# power_fix.net
KiCad netlist of a schematic drawn in Altium Designer
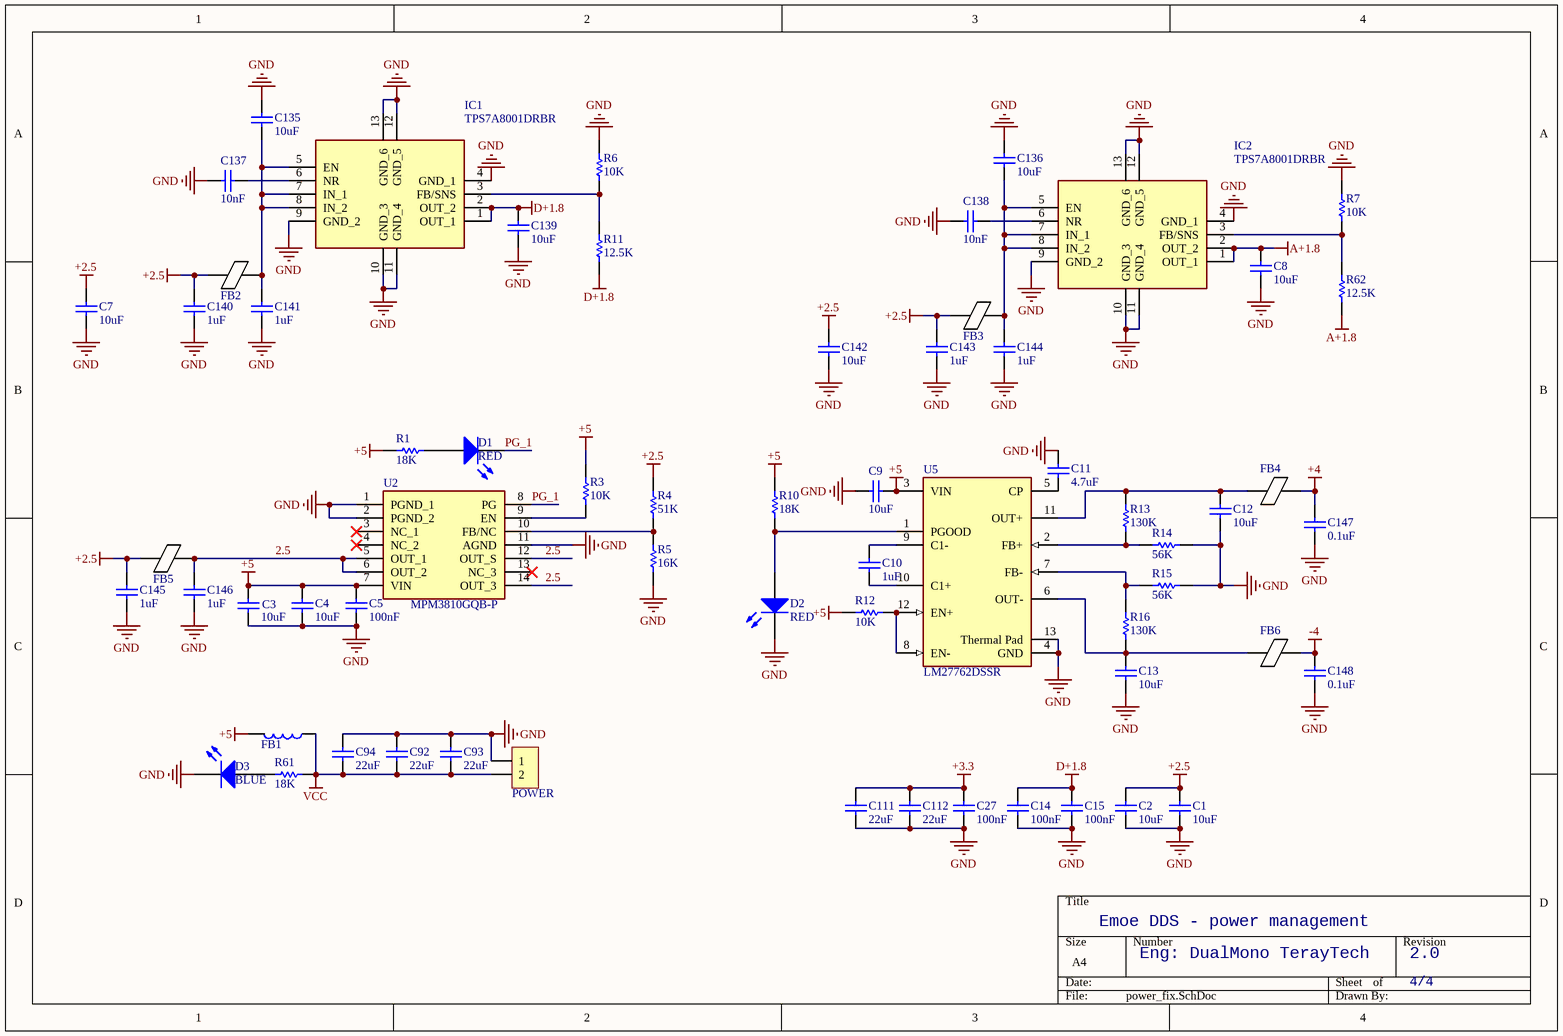
[diagram p0: power_fix.SchDoc]

(export (version "E")
  (design (tool "Eeschema 10.0.6"))
  (components
    (comp (ref "C1")
      (value "10uF")
      (footprint "1608[0603]")
      (description "Capacitor")
      (fields (field (name "PUBLISHER") "Altium Limited"))
      (libsource (lib "My Footprint") (part "CAP"))
    )
    (comp (ref "C2")
      (value "10uF")
      (footprint "1608[0603]")
      (description "Capacitor")
      (fields (field (name "PUBLISHER") "Altium Limited"))
      (libsource (lib "My Footprint") (part "CAP"))
    )
    (comp (ref "C3")
      (value "10uF")
      (footprint "1608[0603]")
      (description "Capacitor")
      (fields (field (name "PUBLISHER") "Altium Limited"))
      (libsource (lib "My Footprint") (part "CAP"))
    )
    (comp (ref "C4")
      (value "10uF")
      (footprint "1608[0603]")
      (description "Capacitor")
      (fields (field (name "PUBLISHER") "Altium Limited"))
      (libsource (lib "My Footprint") (part "CAP"))
    )
    (comp (ref "C5")
      (value "100nF")
      (footprint "0402")
      (description "Capacitor")
      (fields (field (name "PUBLISHER") "Altium Limited"))
      (libsource (lib "My Footprint") (part "CAP"))
    )
    (comp (ref "C7")
      (value "10uF")
      (footprint "1608[0603]")
      (description "Capacitor")
      (fields (field (name "PUBLISHER") "Altium Limited"))
      (libsource (lib "My Footprint") (part "CAP"))
    )
    (comp (ref "C8")
      (value "10uF")
      (footprint "0603_C")
      (description "Capacitor")
      (fields (field (name "PUBLISHER") "Altium Limited"))
      (libsource (lib "My Footprint") (part "CAP"))
    )
    (comp (ref "C9")
      (value "10uF")
      (footprint "1608[0603]")
      (description "Capacitor")
      (fields (field (name "PUBLISHER") "Altium Limited"))
      (libsource (lib "My Footprint") (part "CAP"))
    )
    (comp (ref "C10")
      (value "1uF")
      (footprint "0402")
      (description "Capacitor")
      (fields (field (name "PUBLISHER") "Altium Limited"))
      (libsource (lib "My Footprint") (part "CAP"))
    )
    (comp (ref "C11")
      (value "4.7uF")
      (footprint "1608[0603]")
      (description "Capacitor")
      (fields (field (name "PUBLISHER") "Altium Limited"))
      (libsource (lib "My Footprint") (part "CAP"))
    )
    (comp (ref "C12")
      (value "10uF")
      (footprint "1608[0603]")
      (description "Capacitor")
      (fields (field (name "PUBLISHER") "Altium Limited"))
      (libsource (lib "My Footprint") (part "CAP"))
    )
    (comp (ref "C13")
      (value "10uF")
      (footprint "1608[0603]")
      (description "Capacitor")
      (fields (field (name "PUBLISHER") "Altium Limited"))
      (libsource (lib "My Footprint") (part "CAP"))
    )
    (comp (ref "C14")
      (value "100nF")
      (footprint "0402")
      (description "Capacitor")
      (fields (field (name "PUBLISHER") "Altium Limited"))
      (libsource (lib "My Footprint") (part "CAP"))
    )
    (comp (ref "C15")
      (value "100nF")
      (footprint "0402")
      (description "Capacitor")
      (fields (field (name "PUBLISHER") "Altium Limited"))
      (libsource (lib "My Footprint") (part "CAP"))
    )
    (comp (ref "C27")
      (value "100nF")
      (footprint "0402")
      (description "Capacitor")
      (fields (field (name "PUBLISHER") "Altium Limited"))
      (libsource (lib "My Footprint") (part "CAP"))
    )
    (comp (ref "C92")
      (value "22uF")
      (footprint "6-0805_L")
      (description "Capacitor")
      (fields (field (name "PUBLISHER") "Altium Limited"))
      (libsource (lib "My Footprint") (part "CAP"))
    )
    (comp (ref "C93")
      (value "22uF")
      (footprint "6-0805_L")
      (description "Capacitor")
      (fields (field (name "PUBLISHER") "Altium Limited"))
      (libsource (lib "My Footprint") (part "CAP"))
    )
    (comp (ref "C94")
      (value "22uF")
      (footprint "6-0805_L")
      (description "Capacitor")
      (fields (field (name "PUBLISHER") "Altium Limited"))
      (libsource (lib "My Footprint") (part "CAP"))
    )
    (comp (ref "C111")
      (value "22uF")
      (footprint "6-0805_L")
      (description "Capacitor")
      (fields (field (name "PUBLISHER") "Altium Limited"))
      (libsource (lib "My Footprint") (part "CAP"))
    )
    (comp (ref "C112")
      (value "22uF")
      (footprint "6-0805_L")
      (description "Capacitor")
      (fields (field (name "PUBLISHER") "Altium Limited"))
      (libsource (lib "My Footprint") (part "CAP"))
    )
    (comp (ref "C135")
      (value "10uF")
      (footprint "0603_C")
      (description "Capacitor")
      (fields (field (name "PUBLISHER") "Altium Limited"))
      (libsource (lib "My Footprint") (part "CAP"))
    )
    (comp (ref "C136")
      (value "10uF")
      (footprint "0603_C")
      (description "Capacitor")
      (fields (field (name "PUBLISHER") "Altium Limited"))
      (libsource (lib "My Footprint") (part "CAP"))
    )
    (comp (ref "C137")
      (value "10nF")
      (footprint "0402L")
      (description "Capacitor")
      (fields (field (name "PUBLISHER") "Altium Limited"))
      (libsource (lib "My Footprint") (part "CAP"))
    )
    (comp (ref "C138")
      (value "10nF")
      (footprint "0402L")
      (description "Capacitor")
      (fields (field (name "PUBLISHER") "Altium Limited"))
      (libsource (lib "My Footprint") (part "CAP"))
    )
    (comp (ref "C139")
      (value "10uF")
      (footprint "0603_C")
      (description "Capacitor")
      (fields (field (name "PUBLISHER") "Altium Limited"))
      (libsource (lib "My Footprint") (part "CAP"))
    )
    (comp (ref "C140")
      (value "1uF")
      (footprint "0603_C")
      (description "Capacitor")
      (fields (field (name "PUBLISHER") "Altium Limited"))
      (libsource (lib "My Footprint") (part "CAP"))
    )
    (comp (ref "C141")
      (value "1uF")
      (footprint "0603_C")
      (description "Capacitor")
      (fields (field (name "PUBLISHER") "Altium Limited"))
      (libsource (lib "My Footprint") (part "CAP"))
    )
    (comp (ref "C142")
      (value "10uF")
      (footprint "0603_C")
      (description "Capacitor")
      (fields (field (name "PUBLISHER") "Altium Limited"))
      (libsource (lib "My Footprint") (part "CAP"))
    )
    (comp (ref "C143")
      (value "1uF")
      (footprint "0603_C")
      (description "Capacitor")
      (fields (field (name "PUBLISHER") "Altium Limited"))
      (libsource (lib "My Footprint") (part "CAP"))
    )
    (comp (ref "C144")
      (value "1uF")
      (footprint "0603_C")
      (description "Capacitor")
      (fields (field (name "PUBLISHER") "Altium Limited"))
      (libsource (lib "My Footprint") (part "CAP"))
    )
    (comp (ref "C145")
      (value "1uF")
      (footprint "0603_C")
      (description "Capacitor")
      (fields (field (name "PUBLISHER") "Altium Limited"))
      (libsource (lib "My Footprint") (part "CAP"))
    )
    (comp (ref "C146")
      (value "1uF")
      (footprint "0603_C")
      (description "Capacitor")
      (fields (field (name "PUBLISHER") "Altium Limited"))
      (libsource (lib "My Footprint") (part "CAP"))
    )
    (comp (ref "C147")
      (value "0.1uF")
      (footprint "0603_C")
      (description "Capacitor")
      (fields (field (name "PUBLISHER") "Altium Limited"))
      (libsource (lib "My Footprint") (part "CAP"))
    )
    (comp (ref "C148")
      (value "0.1uF")
      (footprint "0603_C")
      (description "Capacitor")
      (fields (field (name "PUBLISHER") "Altium Limited"))
      (libsource (lib "My Footprint") (part "CAP"))
    )
    (comp (ref "D1")
      (value "RED")
      (footprint "1608[0603]")
      (description "Typical INFRARED GaAs LED")
      (fields (field (name "PUBLISHER") "Altium Limited"))
      (libsource (lib "Miscellaneous Devices") (part "LED0"))
    )
    (comp (ref "D2")
      (value "RED")
      (footprint "1608[0603]")
      (description "Typical INFRARED GaAs LED")
      (fields (field (name "PUBLISHER") "Altium Limited"))
      (libsource (lib "Miscellaneous Devices") (part "LED0"))
    )
    (comp (ref "D3")
      (value "BLUE")
      (footprint "1608[0603]")
      (description "Typical INFRARED GaAs LED")
      (fields (field (name "PUBLISHER") "Altium Limited"))
      (libsource (lib "Miscellaneous Devices") (part "LED0"))
    )
    (comp (ref "FB1")
      (value "100R,100MHz, 0603")
      (footprint "1608[0603]")
      (description "磁珠")
      (libsource (lib "") (part "FB_1"))
    )
    (comp (ref "FB2")
      (value "600Ω @ 100MHz")
      (footprint "0603")
      (description "磁珠 600Ω @ 100MHz")
      (libsource (lib "My Footprint") (part "FB"))
    )
    (comp (ref "FB3")
      (value "600Ω @ 100MHz")
      (footprint "0603")
      (description "磁珠 600Ω @ 100MHz")
      (libsource (lib "My Footprint") (part "FB"))
    )
    (comp (ref "FB4")
      (value "600Ω @ 100MHz")
      (footprint "0603")
      (description "磁珠 600Ω @ 100MHz")
      (libsource (lib "My Footprint") (part "FB"))
    )
    (comp (ref "FB5")
      (value "600Ω @ 100MHz")
      (footprint "0603")
      (description "磁珠 600Ω @ 100MHz")
      (libsource (lib "My Footprint") (part "FB"))
    )
    (comp (ref "FB6")
      (value "600Ω @ 100MHz")
      (footprint "0603")
      (description "磁珠 600Ω @ 100MHz")
      (libsource (lib "My Footprint") (part "FB"))
    )
    (comp (ref "IC1")
      (value "TPS7A8001DRBR")
      (footprint "SamacSys:TPS7A8001DRBR")
      (description "Integrated Circuit")
      (fields (field (name "MOUSER PART NUMBER") "595-TPS7A8001DRBR"))
      (libsource (lib "SamacSys") (part "TPS7A8001DRBR"))
    )
    (comp (ref "IC2")
      (value "TPS7A8001DRBR")
      (footprint "SamacSys:TPS7A8001DRBR")
      (description "Integrated Circuit")
      (fields (field (name "MOUSER PART NUMBER") "595-TPS7A8001DRBR"))
      (libsource (lib "SamacSys") (part "TPS7A8001DRBR"))
    )
    (comp (ref "POWER")
      (value "HDR-1X2")
      (footprint "KF2510-LI-2P")
      (description "2P接插件")
      (libsource (lib "2510_2P") (part "Header 2"))
    )
    (comp (ref "R1")
      (value "18K")
      (footprint "0402")
      (description "Resistor")
      (fields (field (name "PUBLISHER") "Altium Limited"))
      (libsource (lib "My Footprint") (part "RES"))
    )
    (comp (ref "R3")
      (value "10K")
      (footprint "0402")
      (description "Resistor")
      (fields (field (name "PUBLISHER") "Altium Limited"))
      (libsource (lib "My Footprint") (part "RES"))
    )
    (comp (ref "R4")
      (value "51K")
      (footprint "0402")
      (description "Resistor")
      (fields (field (name "PUBLISHER") "Altium Limited"))
      (libsource (lib "My Footprint") (part "RES"))
    )
    (comp (ref "R5")
      (value "16K")
      (footprint "0402")
      (description "Resistor")
      (fields (field (name "PUBLISHER") "Altium Limited"))
      (libsource (lib "My Footprint") (part "RES"))
    )
    (comp (ref "R6")
      (value "10K")
      (footprint "0402L")
      (description "Resistor")
      (fields (field (name "PUBLISHER") "Altium Limited"))
      (libsource (lib "My Footprint") (part "RES"))
    )
    (comp (ref "R7")
      (value "10K")
      (footprint "0402L")
      (description "Resistor")
      (fields (field (name "PUBLISHER") "Altium Limited"))
      (libsource (lib "My Footprint") (part "RES"))
    )
    (comp (ref "R10")
      (value "18K")
      (footprint "0402")
      (description "Resistor")
      (fields (field (name "PUBLISHER") "Altium Limited"))
      (libsource (lib "My Footprint") (part "RES"))
    )
    (comp (ref "R11")
      (value "12.5K")
      (footprint "0402L")
      (description "Resistor")
      (fields (field (name "PUBLISHER") "Altium Limited"))
      (libsource (lib "My Footprint") (part "RES"))
    )
    (comp (ref "R12")
      (value "10K")
      (footprint "0402")
      (description "Resistor")
      (fields (field (name "PUBLISHER") "Altium Limited"))
      (libsource (lib "My Footprint") (part "RES"))
    )
    (comp (ref "R13")
      (value "130K")
      (footprint "0402")
      (description "Resistor")
      (fields (field (name "PUBLISHER") "Altium Limited"))
      (libsource (lib "My Footprint") (part "RES"))
    )
    (comp (ref "R14")
      (value "56K")
      (footprint "0402")
      (description "Resistor")
      (fields (field (name "PUBLISHER") "Altium Limited"))
      (libsource (lib "My Footprint") (part "RES"))
    )
    (comp (ref "R15")
      (value "56K")
      (footprint "0402")
      (description "Resistor")
      (fields (field (name "PUBLISHER") "Altium Limited"))
      (libsource (lib "My Footprint") (part "RES"))
    )
    (comp (ref "R16")
      (value "130K")
      (footprint "0402")
      (description "Resistor")
      (fields (field (name "PUBLISHER") "Altium Limited"))
      (libsource (lib "My Footprint") (part "RES"))
    )
    (comp (ref "R61")
      (value "18K")
      (footprint "0402")
      (description "Resistor")
      (fields (field (name "PUBLISHER") "Altium Limited"))
      (libsource (lib "My Footprint") (part "RES"))
    )
    (comp (ref "R62")
      (value "12.5K")
      (footprint "0402L")
      (description "Resistor")
      (fields (field (name "PUBLISHER") "Altium Limited"))
      (libsource (lib "My Footprint") (part "RES"))
    )
    (comp (ref "U2")
      (value "MPM3810GQB-P")
      (footprint "SamacSys:MPM3810GQB33Z")
      (description "Integrated Circuit")
      (fields (field (name "MOUSER PART NUMBER") "946-MPM3810GQBP"))
      (libsource (lib "*") (part "MPM3810GQB-P"))
    )
    (comp (ref "U5")
      (value "LM27762DSSR")
      (footprint "FP-DSS0012B-IPC_A")
      (description "IC REG CHARGE PUMP ADJ DL 12WSON")
      (libsource (lib "LM27762") (part "CMP-04918-000139-2"))
    )
  )
  (nets
    (net (code "1") (name "+2.5") (class "Default")
      (node (ref "C1") (pin "2") (pinfunction "2_2") (pintype "passive"))
      (node (ref "C140") (pin "2") (pinfunction "2_2") (pintype "passive"))
      (node (ref "C142") (pin "2") (pinfunction "2_2") (pintype "passive"))
      (node (ref "C143") (pin "2") (pinfunction "2_2") (pintype "passive"))
      (node (ref "C145") (pin "2") (pinfunction "2_2") (pintype "passive"))
      (node (ref "C2") (pin "2") (pinfunction "2_2") (pintype "passive"))
      (node (ref "C7") (pin "1") (pinfunction "1_1") (pintype "passive"))
      (node (ref "FB2") (pin "1") (pinfunction "1_1") (pintype "passive"))
      (node (ref "FB3") (pin "1") (pinfunction "1_1") (pintype "passive"))
      (node (ref "FB5") (pin "1") (pinfunction "1_1") (pintype "passive"))
      (node (ref "R4") (pin "2") (pinfunction "2_2") (pintype "passive"))
    )
    (net (code "2") (name "+3.3") (class "Default")
      (node (ref "C111") (pin "1") (pinfunction "1_1") (pintype "passive"))
      (node (ref "C112") (pin "1") (pinfunction "1_1") (pintype "passive"))
      (node (ref "C27") (pin "1") (pinfunction "1_1") (pintype "passive"))
    )
    (net (code "3") (name "+4") (class "Default")
      (node (ref "C147") (pin "2") (pinfunction "2_2") (pintype "passive"))
      (node (ref "FB4") (pin "1") (pinfunction "1_1") (pintype "passive"))
    )
    (net (code "4") (name "+5") (class "Default")
      (node (ref "C3") (pin "1") (pinfunction "1_1") (pintype "passive"))
      (node (ref "C4") (pin "1") (pinfunction "1_1") (pintype "passive"))
      (node (ref "C5") (pin "1") (pinfunction "1_1") (pintype "passive"))
      (node (ref "C9") (pin "2") (pinfunction "2_2") (pintype "passive"))
      (node (ref "FB1") (pin "2") (pinfunction "2_2") (pintype "passive"))
      (node (ref "R1") (pin "2") (pinfunction "2_2") (pintype "passive"))
      (node (ref "R10") (pin "2") (pinfunction "2_2") (pintype "passive"))
      (node (ref "R12") (pin "1") (pinfunction "1_1") (pintype "passive"))
      (node (ref "R3") (pin "2") (pinfunction "2_2") (pintype "passive"))
      (node (ref "U2") (pin "7") (pinfunction "VIN_7") (pintype "passive"))
      (node (ref "U5") (pin "3") (pinfunction "VIN_3") (pintype "power_in"))
    )
    (net (code "5") (name "-4") (class "Default")
      (node (ref "C148") (pin "2") (pinfunction "2_2") (pintype "passive"))
      (node (ref "FB6") (pin "1") (pinfunction "1_1") (pintype "passive"))
    )
    (net (code "6") (name "/2.5") (class "Default")
      (node (ref "C146") (pin "2") (pinfunction "2_2") (pintype "passive"))
      (node (ref "FB5") (pin "2") (pinfunction "2_2") (pintype "passive"))
      (node (ref "U2") (pin "12") (pinfunction "OUT_S_12") (pintype "passive"))
      (node (ref "U2") (pin "14") (pinfunction "OUT_3_14") (pintype "passive"))
      (node (ref "U2") (pin "5") (pinfunction "OUT_1_5") (pintype "passive"))
      (node (ref "U2") (pin "6") (pinfunction "OUT_2_6") (pintype "passive"))
    )
    (net (code "7") (name "/PG_1") (class "Default")
      (node (ref "D1") (pin "2") (pinfunction "K_2") (pintype "passive"))
      (node (ref "U2") (pin "8") (pinfunction "PG_8") (pintype "passive"))
    )
    (net (code "8") (name "A+1.8") (class "Default")
      (node (ref "C8") (pin "2") (pinfunction "2_2") (pintype "passive"))
      (node (ref "IC2") (pin "1") (pinfunction "OUT_1_1") (pintype "passive"))
      (node (ref "IC2") (pin "2") (pinfunction "OUT_2_2") (pintype "passive"))
      (node (ref "R62") (pin "1") (pinfunction "1_1") (pintype "passive"))
    )
    (net (code "9") (name "D+1.8") (class "Default")
      (node (ref "C139") (pin "2") (pinfunction "2_2") (pintype "passive"))
      (node (ref "C14") (pin "1") (pinfunction "1_1") (pintype "passive"))
      (node (ref "C15") (pin "1") (pinfunction "1_1") (pintype "passive"))
      (node (ref "IC1") (pin "1") (pinfunction "OUT_1_1") (pintype "passive"))
      (node (ref "IC1") (pin "2") (pinfunction "OUT_2_2") (pintype "passive"))
      (node (ref "R11") (pin "1") (pinfunction "1_1") (pintype "passive"))
    )
    (net (code "10") (name "GND") (class "Default")
      (node (ref "C1") (pin "1") (pinfunction "1_1") (pintype "passive"))
      (node (ref "C11") (pin "2") (pinfunction "2_2") (pintype "passive"))
      (node (ref "C111") (pin "2") (pinfunction "2_2") (pintype "passive"))
      (node (ref "C112") (pin "2") (pinfunction "2_2") (pintype "passive"))
      (node (ref "C12") (pin "2") (pinfunction "2_2") (pintype "passive"))
      (node (ref "C13") (pin "1") (pinfunction "1_1") (pintype "passive"))
      (node (ref "C135") (pin "1") (pinfunction "1_1") (pintype "passive"))
      (node (ref "C136") (pin "1") (pinfunction "1_1") (pintype "passive"))
      (node (ref "C137") (pin "1") (pinfunction "1_1") (pintype "passive"))
      (node (ref "C138") (pin "1") (pinfunction "1_1") (pintype "passive"))
      (node (ref "C139") (pin "1") (pinfunction "1_1") (pintype "passive"))
      (node (ref "C14") (pin "2") (pinfunction "2_2") (pintype "passive"))
      (node (ref "C140") (pin "1") (pinfunction "1_1") (pintype "passive"))
      (node (ref "C141") (pin "1") (pinfunction "1_1") (pintype "passive"))
      (node (ref "C142") (pin "1") (pinfunction "1_1") (pintype "passive"))
      (node (ref "C143") (pin "1") (pinfunction "1_1") (pintype "passive"))
      (node (ref "C144") (pin "1") (pinfunction "1_1") (pintype "passive"))
      (node (ref "C145") (pin "1") (pinfunction "1_1") (pintype "passive"))
      (node (ref "C146") (pin "1") (pinfunction "1_1") (pintype "passive"))
      (node (ref "C147") (pin "1") (pinfunction "1_1") (pintype "passive"))
      (node (ref "C148") (pin "1") (pinfunction "1_1") (pintype "passive"))
      (node (ref "C15") (pin "2") (pinfunction "2_2") (pintype "passive"))
      (node (ref "C2") (pin "1") (pinfunction "1_1") (pintype "passive"))
      (node (ref "C27") (pin "2") (pinfunction "2_2") (pintype "passive"))
      (node (ref "C3") (pin "2") (pinfunction "2_2") (pintype "passive"))
      (node (ref "C4") (pin "2") (pinfunction "2_2") (pintype "passive"))
      (node (ref "C5") (pin "2") (pinfunction "2_2") (pintype "passive"))
      (node (ref "C7") (pin "2") (pinfunction "2_2") (pintype "passive"))
      (node (ref "C8") (pin "1") (pinfunction "1_1") (pintype "passive"))
      (node (ref "C9") (pin "1") (pinfunction "1_1") (pintype "passive"))
      (node (ref "C92") (pin "2") (pinfunction "2_2") (pintype "passive"))
      (node (ref "C93") (pin "2") (pinfunction "2_2") (pintype "passive"))
      (node (ref "C94") (pin "2") (pinfunction "2_2") (pintype "passive"))
      (node (ref "D2") (pin "2") (pinfunction "K_2") (pintype "passive"))
      (node (ref "D3") (pin "2") (pinfunction "K_2") (pintype "passive"))
      (node (ref "IC1") (pin "10") (pinfunction "GND_3_10") (pintype "passive"))
      (node (ref "IC1") (pin "11") (pinfunction "GND_4_11") (pintype "passive"))
      (node (ref "IC1") (pin "12") (pinfunction "GND_5_12") (pintype "passive"))
      (node (ref "IC1") (pin "13") (pinfunction "GND_6_13") (pintype "passive"))
      (node (ref "IC1") (pin "4") (pinfunction "GND_1_4") (pintype "passive"))
      (node (ref "IC1") (pin "9") (pinfunction "GND_2_9") (pintype "passive"))
      (node (ref "IC2") (pin "10") (pinfunction "GND_3_10") (pintype "passive"))
      (node (ref "IC2") (pin "11") (pinfunction "GND_4_11") (pintype "passive"))
      (node (ref "IC2") (pin "12") (pinfunction "GND_5_12") (pintype "passive"))
      (node (ref "IC2") (pin "13") (pinfunction "GND_6_13") (pintype "passive"))
      (node (ref "IC2") (pin "4") (pinfunction "GND_1_4") (pintype "passive"))
      (node (ref "IC2") (pin "9") (pinfunction "GND_2_9") (pintype "passive"))
      (node (ref "POWER") (pin "1") (pinfunction "1_1") (pintype "passive"))
      (node (ref "R14") (pin "1") (pinfunction "1_1") (pintype "passive"))
      (node (ref "R15") (pin "1") (pinfunction "1_1") (pintype "passive"))
      (node (ref "R5") (pin "1") (pinfunction "1_1") (pintype "passive"))
      (node (ref "R6") (pin "2") (pinfunction "2_2") (pintype "passive"))
      (node (ref "R7") (pin "2") (pinfunction "2_2") (pintype "passive"))
      (node (ref "U2") (pin "1") (pinfunction "PGND_1_1") (pintype "passive"))
      (node (ref "U2") (pin "11") (pinfunction "AGND_11") (pintype "passive"))
      (node (ref "U2") (pin "2") (pinfunction "PGND_2_2") (pintype "passive"))
      (node (ref "U5") (pin "13") (pinfunction "Thermal_Pad_13") (pintype "passive"))
      (node (ref "U5") (pin "4") (pinfunction "GND_4") (pintype "power_in"))
    )
    (net (code "11") (name "Net-(D1-A)") (class "Default")
      (node (ref "D1") (pin "1") (pinfunction "A_1") (pintype "passive"))
      (node (ref "R1") (pin "1") (pinfunction "1_1") (pintype "passive"))
    )
    (net (code "12") (name "Net-(D2-A)") (class "Default")
      (node (ref "D2") (pin "1") (pinfunction "A_1") (pintype "passive"))
      (node (ref "R10") (pin "1") (pinfunction "1_1") (pintype "passive"))
      (node (ref "U5") (pin "1") (pinfunction "PGOOD_1") (pintype "open_collector"))
    )
    (net (code "13") (name "Net-(D3-A)") (class "Default")
      (node (ref "D3") (pin "1") (pinfunction "A_1") (pintype "passive"))
      (node (ref "R61") (pin "2") (pinfunction "2_2") (pintype "passive"))
    )
    (net (code "14") (name "Net-(IC1-EN)") (class "Default")
      (node (ref "C135") (pin "2") (pinfunction "2_2") (pintype "passive"))
      (node (ref "C141") (pin "2") (pinfunction "2_2") (pintype "passive"))
      (node (ref "FB2") (pin "2") (pinfunction "2_2") (pintype "passive"))
      (node (ref "IC1") (pin "5") (pinfunction "EN_5") (pintype "passive"))
      (node (ref "IC1") (pin "7") (pinfunction "IN_1_7") (pintype "passive"))
      (node (ref "IC1") (pin "8") (pinfunction "IN_2_8") (pintype "passive"))
    )
    (net (code "15") (name "Net-(IC1-FB{slash}SNS)") (class "Default")
      (node (ref "IC1") (pin "3") (pinfunction "FB/SNS_3") (pintype "passive"))
      (node (ref "R11") (pin "2") (pinfunction "2_2") (pintype "passive"))
      (node (ref "R6") (pin "1") (pinfunction "1_1") (pintype "passive"))
    )
    (net (code "16") (name "Net-(IC1-NR)") (class "Default")
      (node (ref "C137") (pin "2") (pinfunction "2_2") (pintype "passive"))
      (node (ref "IC1") (pin "6") (pinfunction "NR_6") (pintype "passive"))
    )
    (net (code "17") (name "Net-(IC2-EN)") (class "Default")
      (node (ref "C136") (pin "2") (pinfunction "2_2") (pintype "passive"))
      (node (ref "C144") (pin "2") (pinfunction "2_2") (pintype "passive"))
      (node (ref "FB3") (pin "2") (pinfunction "2_2") (pintype "passive"))
      (node (ref "IC2") (pin "5") (pinfunction "EN_5") (pintype "passive"))
      (node (ref "IC2") (pin "7") (pinfunction "IN_1_7") (pintype "passive"))
      (node (ref "IC2") (pin "8") (pinfunction "IN_2_8") (pintype "passive"))
    )
    (net (code "18") (name "Net-(IC2-FB{slash}SNS)") (class "Default")
      (node (ref "IC2") (pin "3") (pinfunction "FB/SNS_3") (pintype "passive"))
      (node (ref "R62") (pin "2") (pinfunction "2_2") (pintype "passive"))
      (node (ref "R7") (pin "1") (pinfunction "1_1") (pintype "passive"))
    )
    (net (code "19") (name "Net-(IC2-NR)") (class "Default")
      (node (ref "C138") (pin "2") (pinfunction "2_2") (pintype "passive"))
      (node (ref "IC2") (pin "6") (pinfunction "NR_6") (pintype "passive"))
    )
    (net (code "20") (name "Net-(U2-EN)") (class "Default")
      (node (ref "R3") (pin "1") (pinfunction "1_1") (pintype "passive"))
      (node (ref "U2") (pin "9") (pinfunction "EN_9") (pintype "passive"))
    )
    (net (code "21") (name "Net-(U2-FB{slash}NC)") (class "Default")
      (node (ref "R4") (pin "1") (pinfunction "1_1") (pintype "passive"))
      (node (ref "R5") (pin "2") (pinfunction "2_2") (pintype "passive"))
      (node (ref "U2") (pin "10") (pinfunction "FB/NC_10") (pintype "passive"))
    )
    (net (code "22") (name "Net-(U5-C1+)") (class "Default")
      (node (ref "C10") (pin "1") (pinfunction "1_1") (pintype "passive"))
      (node (ref "U5") (pin "10") (pinfunction "C1+_10") (pintype "passive"))
    )
    (net (code "23") (name "Net-(U5-C1-)") (class "Default")
      (node (ref "C10") (pin "2") (pinfunction "2_2") (pintype "passive"))
      (node (ref "U5") (pin "9") (pinfunction "C1-_9") (pintype "passive"))
    )
    (net (code "24") (name "Net-(U5-CP)") (class "Default")
      (node (ref "C11") (pin "1") (pinfunction "1_1") (pintype "passive"))
      (node (ref "U5") (pin "5") (pinfunction "CP_5") (pintype "passive"))
    )
    (net (code "25") (name "Net-(U5-EN+)") (class "Default")
      (node (ref "R12") (pin "2") (pinfunction "2_2") (pintype "passive"))
      (node (ref "U5") (pin "12") (pinfunction "EN+_12") (pintype "input"))
      (node (ref "U5") (pin "8") (pinfunction "EN-_8") (pintype "input"))
    )
    (net (code "26") (name "Net-(U5-FB+)") (class "Default")
      (node (ref "R13") (pin "2") (pinfunction "2_2") (pintype "passive"))
      (node (ref "R14") (pin "2") (pinfunction "2_2") (pintype "passive"))
      (node (ref "U5") (pin "2") (pinfunction "FB+_2") (pintype "input"))
    )
    (net (code "27") (name "Net-(U5-FB-)") (class "Default")
      (node (ref "R15") (pin "2") (pinfunction "2_2") (pintype "passive"))
      (node (ref "R16") (pin "1") (pinfunction "1_1") (pintype "passive"))
      (node (ref "U5") (pin "7") (pinfunction "FB-_7") (pintype "input"))
    )
    (net (code "28") (name "Net-(U5-OUT+)") (class "Default")
      (node (ref "C12") (pin "1") (pinfunction "1_1") (pintype "passive"))
      (node (ref "FB4") (pin "2") (pinfunction "2_2") (pintype "passive"))
      (node (ref "R13") (pin "1") (pinfunction "1_1") (pintype "passive"))
      (node (ref "U5") (pin "11") (pinfunction "OUT+_11") (pintype "passive"))
    )
    (net (code "29") (name "Net-(U5-OUT-)") (class "Default")
      (node (ref "C13") (pin "2") (pinfunction "2_2") (pintype "passive"))
      (node (ref "FB6") (pin "2") (pinfunction "2_2") (pintype "passive"))
      (node (ref "R16") (pin "2") (pinfunction "2_2") (pintype "passive"))
      (node (ref "U5") (pin "6") (pinfunction "OUT-_6") (pintype "passive"))
    )
    (net (code "30") (name "VCC") (class "Default")
      (node (ref "C92") (pin "1") (pinfunction "1_1") (pintype "passive"))
      (node (ref "C93") (pin "1") (pinfunction "1_1") (pintype "passive"))
      (node (ref "C94") (pin "1") (pinfunction "1_1") (pintype "passive"))
      (node (ref "FB1") (pin "1") (pinfunction "1_1") (pintype "passive"))
      (node (ref "POWER") (pin "2") (pinfunction "2_2") (pintype "passive"))
      (node (ref "R61") (pin "1") (pinfunction "1_1") (pintype "passive"))
    )
    (net (code "31") (name "unconnected-(U2-NC_1-Pad3)") (class "Default")
      (node (ref "U2") (pin "3") (pinfunction "NC_1_3") (pintype "passive+no_connect"))
    )
    (net (code "32") (name "unconnected-(U2-NC_2-Pad4)") (class "Default")
      (node (ref "U2") (pin "4") (pinfunction "NC_2_4") (pintype "passive+no_connect"))
    )
    (net (code "33") (name "unconnected-(U2-NC_3-Pad13)") (class "Default")
      (node (ref "U2") (pin "13") (pinfunction "NC_3_13") (pintype "passive+no_connect"))
    )
  )
)
